# Adapter_board.net
KiCad netlist of a schematic drawn in Altium Designer
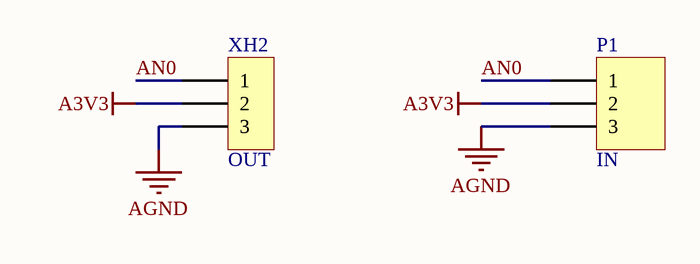
[diagram p0: Adapter board.SchDoc]

(export (version "E")
  (design (tool "Eeschema 10.0.6"))
  (components
    (comp (ref "P1")
      (value "IN")
      (footprint "HDR1X3")
      (description "Header, 3-Pin")
      (fields (field (name "PUBLISHER") "Altium Limited"))
      (libsource (lib "Miscellaneous Connectors") (part "Header 3"))
    )
    (comp (ref "XH2") (value "OUT") (footprint "XH3/2.54mm/180") (libsource (lib "XH，VH") (part "XH3")))
  )
  (nets
    (net (code "1") (name "/AN0") (class "Default")
      (node (ref "P1") (pin "1") (pinfunction "1_1") (pintype "passive"))
      (node (ref "XH2") (pin "1") (pinfunction "1_1") (pintype "passive"))
    )
    (net (code "2") (name "A3V3") (class "Default")
      (node (ref "P1") (pin "2") (pinfunction "2_2") (pintype "passive"))
      (node (ref "XH2") (pin "2") (pinfunction "2_2") (pintype "passive"))
    )
    (net (code "3") (name "AGND") (class "Default")
      (node (ref "P1") (pin "3") (pinfunction "3_3") (pintype "passive"))
      (node (ref "XH2") (pin "3") (pinfunction "3_3") (pintype "passive"))
    )
  )
)
